# PROC091F_FLASH_USB_TO_UART.net
KiCad netlist of a schematic drawn in Altium Designer
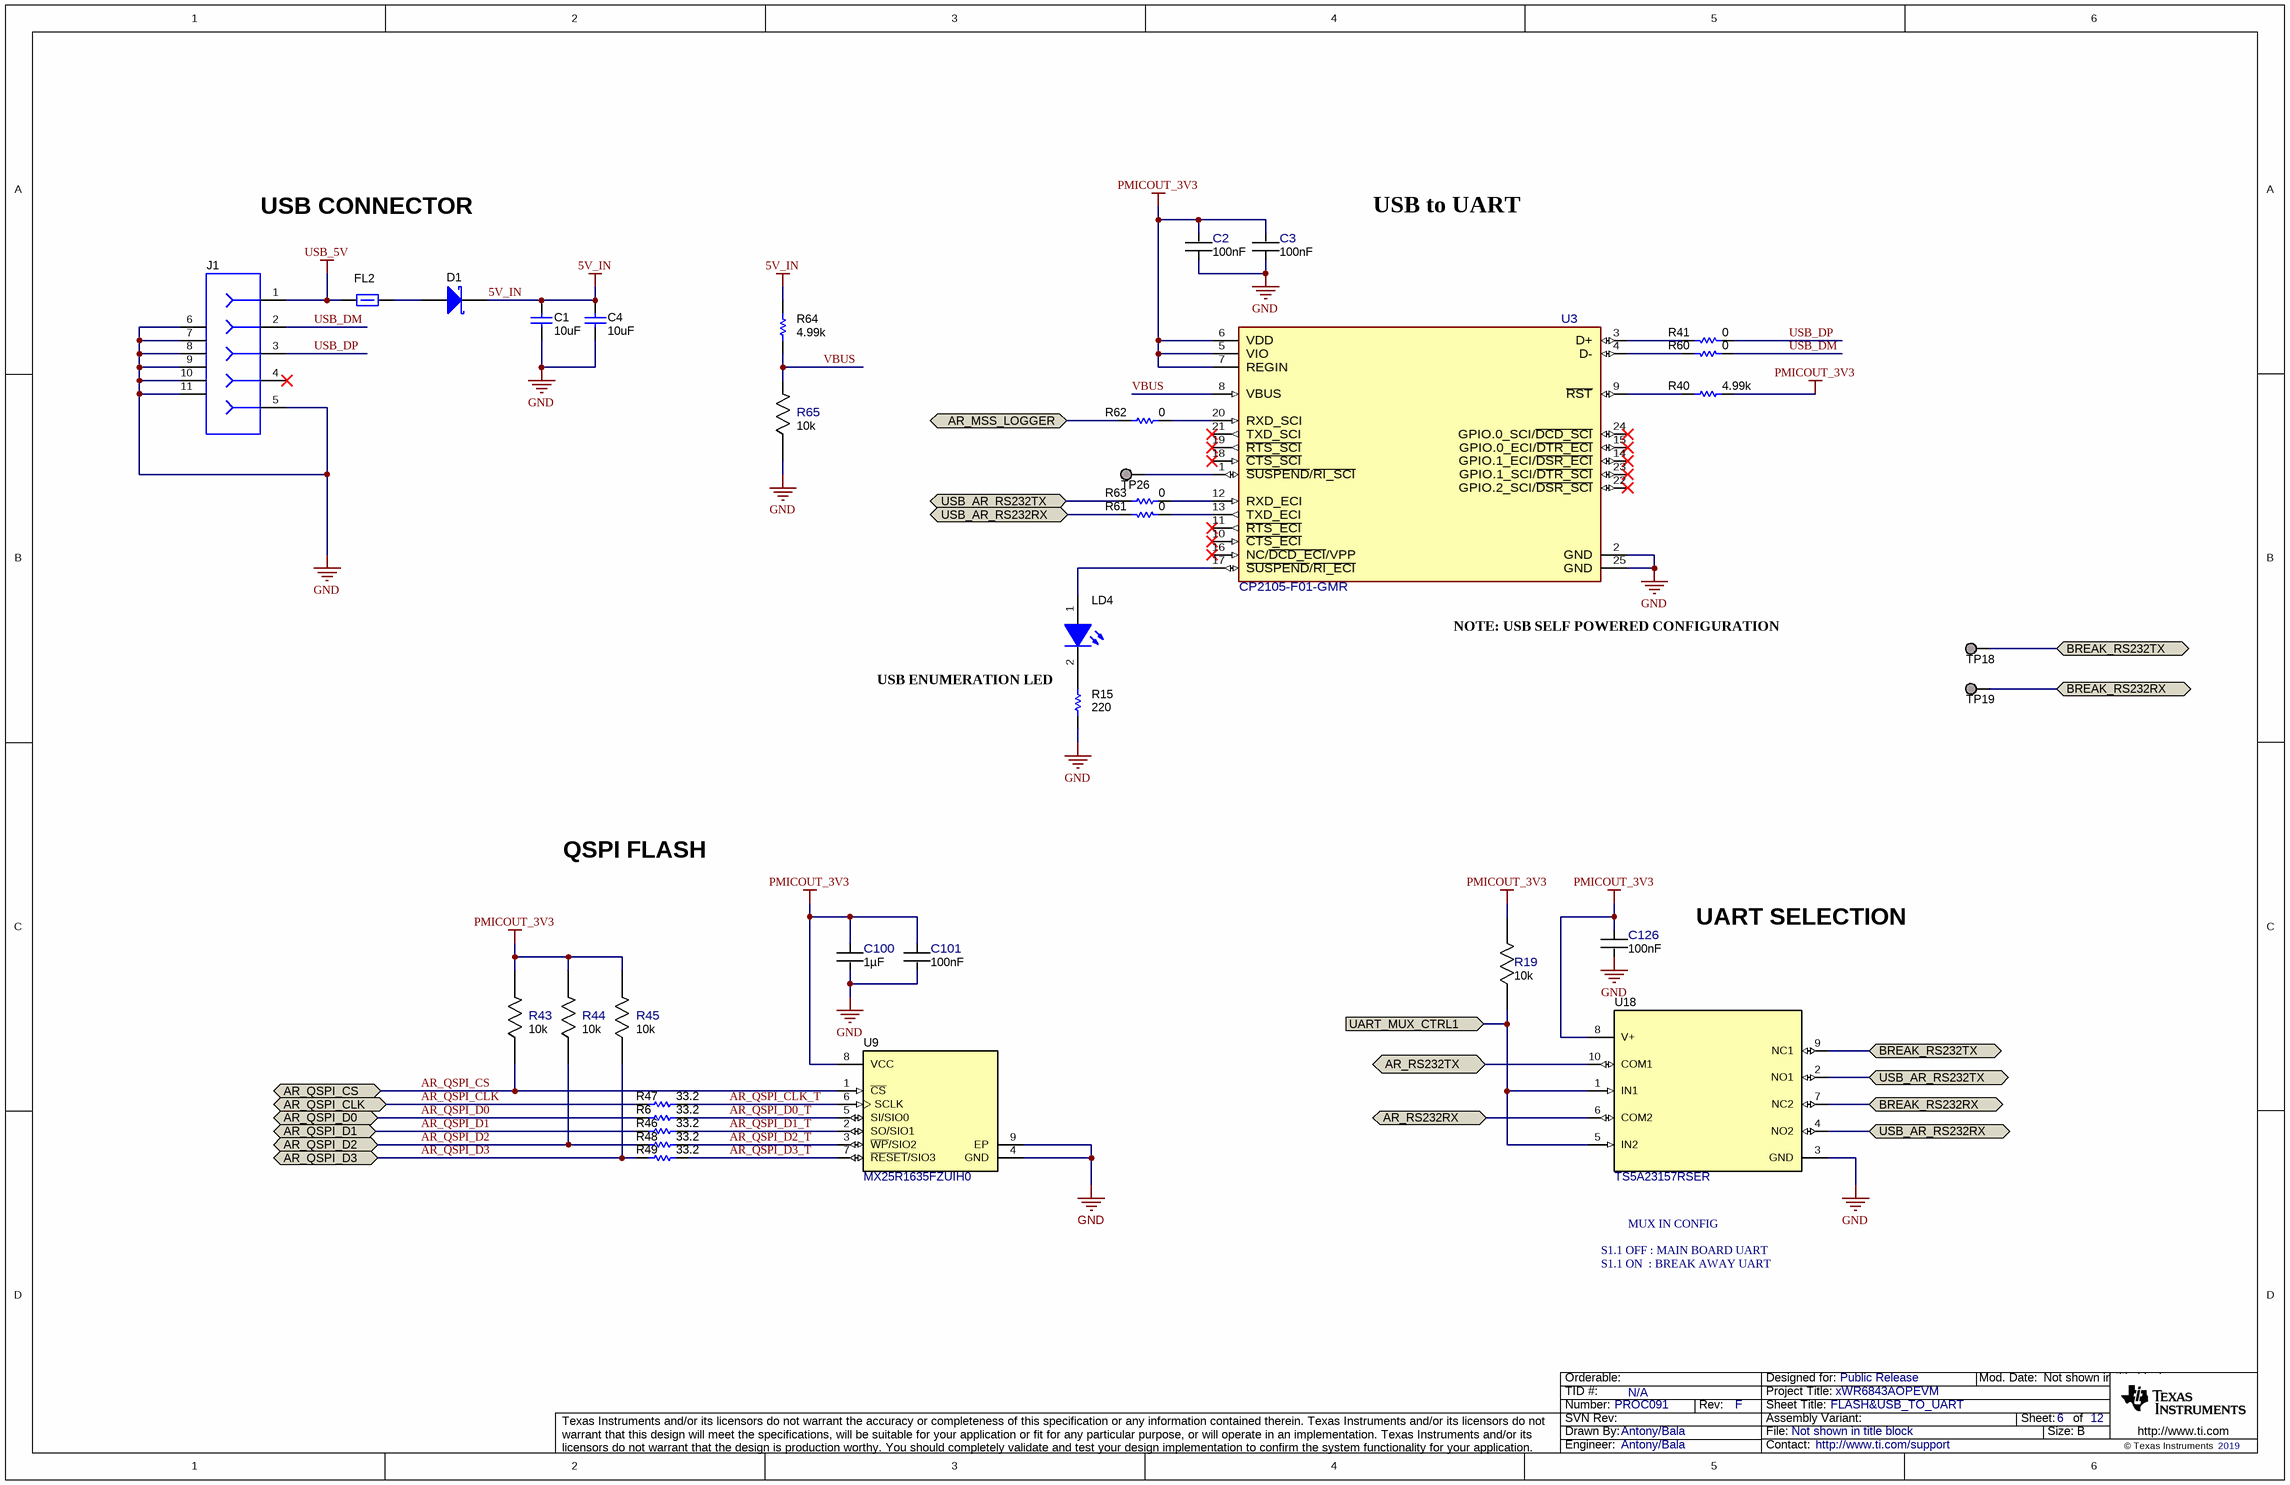
[diagram p0: PROC091F_FLASH_USB_TO_UART.SchDoc]

(export (version "E")
  (design (tool "Eeschema 10.0.6"))
  (components
    (comp (ref "C1")
      (value "10uF")
      (footprint "0402_070")
      (description "CAP, CERM, 10 uF, 10 V, +/- 20%, X5R, 0402")
      (fields
        (field (name "MANUFACTURER") "Samsung Electro-Mechanics")
        (field (name "PARTNUMBER") "CL05A106MP5NUNC")
      )
      (libsource (lib "Altium Vault - TI") (part "Capacitor"))
    )
    (comp (ref "C2")
      (value "GRM033R6YA104KE14D")
      (footprint "FP-GRM033R6YA104KE14D_0201 (0603 Metric)-IPC_C")
      (description "Cap Ceramic 0.1uF 35V X5R 10% Pad SMD 0201 85C T/R")
      (fields (field (name "CAP_F") "100nF") (field (name "MANUFACTURER") "Murata Electronics North America"))
      (libsource (lib "Altium Vault - TI") (part "SYM-B32642B0223J"))
    )
    (comp (ref "C3")
      (value "GRM033R6YA104KE14D")
      (footprint "FP-GRM033R6YA104KE14D_0201 (0603 Metric)-IPC_C")
      (description "Cap Ceramic 0.1uF 35V X5R 10% Pad SMD 0201 85C T/R")
      (fields (field (name "CAP_F") "100nF") (field (name "MANUFACTURER") "Murata Electronics North America"))
      (libsource (lib "Altium Vault - TI") (part "SYM-B32642B0223J"))
    )
    (comp (ref "C4")
      (value "10uF")
      (footprint "0402_070")
      (description "CAP, CERM, 10 uF, 10 V, +/- 20%, X5R, 0402")
      (fields
        (field (name "MANUFACTURER") "Samsung Electro-Mechanics")
        (field (name "PARTNUMBER") "CL05A106MP5NUNC")
      )
      (libsource (lib "Altium Vault - TI") (part "Capacitor"))
    )
    (comp (ref "C100")
      (value "CL03A105MO3NRNH")
      (footprint "FP-CL03A105MO3NRNH_0201-IPC_C")
      (description "1µF ±20% 16V Ceramic Capacitor X5R 0201")
      (fields (field (name "CAP_F") "1µF") (field (name "MANUFACTURER") "Samsung Electro-Mechanics"))
      (libsource (lib "Altium Vault - TI") (part "SYM-B32642B0223J"))
    )
    (comp (ref "C101")
      (value "GRM033R6YA104KE14D")
      (footprint "FP-GRM033R6YA104KE14D_0201 (0603 Metric)-IPC_C")
      (description "Cap Ceramic 0.1uF 35V X5R 10% Pad SMD 0201 85C T/R")
      (fields (field (name "CAP_F") "100nF") (field (name "MANUFACTURER") "Murata Electronics North America"))
      (libsource (lib "Altium Vault - TI") (part "SYM-B32642B0223J"))
    )
    (comp (ref "C126")
      (value "GRM033R6YA104KE14D")
      (footprint "FP-GRM033R6YA104KE14D_0201 (0603 Metric)-IPC_C")
      (description "Cap Ceramic 0.1uF 35V X5R 10% Pad SMD 0201 85C T/R")
      (fields (field (name "CAP_F") "100nF") (field (name "MANUFACTURER") "Murata Electronics North America"))
      (libsource (lib "Altium Vault - TI") (part "SYM-B32642B0223J"))
    )
    (comp (ref "D1")
      (value "NSR20F30NXT5G")
      (footprint "DSN2_0603")
      (description "Diode, Schottky, 30 V, 2 A, 2-XFDFN")
      (fields (field (name "MANUFACTURER") "ON Semiconductor"))
      (libsource (lib "Altium Vault - TI") (part "DIODE_SCHOTTKY"))
    )
    (comp (ref "FL2")
      (value "BLM15PD300SZ1D")
      (footprint "0402L")
      (description "Inductor, Ferrite Bead, Ferrite, 2.2 A, 0.035 ohm, AEC-Q200 Grade 1, SMD")
      (fields (field (name "MANUFACTURER") "MuRata") (field (name "PUBLISHER") "Texas Instruments"))
      (libsource (lib "Altium Vault - TI") (part "Ferrite_Bead"))
    )
    (comp (ref "J1")
      (value "105017-0001")
      (footprint "CONN_105017-0001")
      (description "Connector, Receptacle, Micro-USB Type B, R/A, Bottom Mount SMT")
      (fields (field (name "MANUFACTURER") "Molex") (field (name "PUBLISHER") "Texas Instruments"))
      (libsource (lib "Altium Vault - TI") (part "CONN_105017-0001"))
    )
    (comp (ref "LD4")
      (value "APHHS1005CGCK")
      (footprint "APHHS1005_Green")
      (description "LED, Green, SMD")
      (fields (field (name "MANUFACTURER") "Kingbright"))
      (libsource (lib "Altium Vault - TI") (part "LED"))
    )
    (comp (ref "R6")
      (value "33.2")
      (footprint "0201L")
      (description "RES, 33.2, 1%, 0.05 W, 0201")
      (fields (field (name "MANUFACTURER") "Vishay-Dale") (field (name "PARTNUMBER") "CRCW020133R2FNED"))
      (libsource (lib "Altium Vault - TI") (part "Resistor"))
    )
    (comp (ref "R15")
      (value "220")
      (footprint "0201L")
      (description "RES, 220, 5%, 0.05 W, 0201")
      (fields
        (field (name "MANUFACTURER") "Yageo America")
        (field (name "PARTNUMBER") "RC0201JR-07220RL")
        (field (name "PUBLISHER") "Texas Instruments")
      )
      (libsource (lib "Altium Vault - TI") (part "Resistor"))
    )
    (comp (ref "R19")
      (value "RR0306P-103-D")
      (footprint "FP-RR0306P-103-D_0201-IPC_C")
      (description "10 kOhms ±0.5% 0.05W, 1/20W Chip Resistor 0201 (0603 Metric)  Thin Film")
      (fields (field (name "MANUFACTURER") "Susumu") (field (name "RES_OHM") "10k"))
      (libsource (lib "Altium Vault - TI") (part "SYM-PMR18EZPJ000"))
    )
    (comp (ref "R40")
      (value "4.99k")
      (footprint "0201L")
      (description "RES, 4.99 k, 1%, 0.05 W, 0201")
      (fields
        (field (name "MANUFACTURER") "Yageo America")
        (field (name "PARTNUMBER") "RC0201FR-074K99L")
        (field (name "PUBLISHER") "Texas Instruments")
      )
      (libsource (lib "Altium Vault - TI") (part "Resistor"))
    )
    (comp (ref "R41")
      (value "RC0201JR-070RL")
      (footprint "FP-RC0201JR-070RL_0201 (0603 Metric)-MFG")
      (description "RES SMD 0 OHM JUMPER 1/20W 0201")
      (fields (field (name "MANUFACTURER") "Yageo") (field (name "RES_OHM") "0"))
      (libsource (lib "Altium Vault - TI") (part "SYM-WSR3R1500F"))
    )
    (comp (ref "R43")
      (value "RR0306P-103-D")
      (footprint "FP-RR0306P-103-D_0201-IPC_C")
      (description "10 kOhms ±0.5% 0.05W, 1/20W Chip Resistor 0201 (0603 Metric)  Thin Film")
      (fields (field (name "MANUFACTURER") "Susumu") (field (name "RES_OHM") "10k"))
      (libsource (lib "Altium Vault - TI") (part "SYM-PMR18EZPJ000"))
    )
    (comp (ref "R44")
      (value "RR0306P-103-D")
      (footprint "FP-RR0306P-103-D_0201-IPC_C")
      (description "10 kOhms ±0.5% 0.05W, 1/20W Chip Resistor 0201 (0603 Metric)  Thin Film")
      (fields (field (name "MANUFACTURER") "Susumu") (field (name "RES_OHM") "10k"))
      (libsource (lib "Altium Vault - TI") (part "SYM-PMR18EZPJ000"))
    )
    (comp (ref "R45")
      (value "RR0306P-103-D")
      (footprint "FP-RR0306P-103-D_0201-IPC_C")
      (description "10 kOhms ±0.5% 0.05W, 1/20W Chip Resistor 0201 (0603 Metric)  Thin Film")
      (fields (field (name "MANUFACTURER") "Susumu") (field (name "RES_OHM") "10k"))
      (libsource (lib "Altium Vault - TI") (part "SYM-PMR18EZPJ000"))
    )
    (comp (ref "R46")
      (value "33.2")
      (footprint "0201L")
      (description "RES, 33.2, 1%, 0.05 W, 0201")
      (fields (field (name "MANUFACTURER") "Vishay-Dale") (field (name "PARTNUMBER") "CRCW020133R2FNED"))
      (libsource (lib "Altium Vault - TI") (part "Resistor"))
    )
    (comp (ref "R47")
      (value "33.2")
      (footprint "0201L")
      (description "RES, 33.2, 1%, 0.05 W, 0201")
      (fields (field (name "MANUFACTURER") "Vishay-Dale") (field (name "PARTNUMBER") "CRCW020133R2FNED"))
      (libsource (lib "Altium Vault - TI") (part "Resistor"))
    )
    (comp (ref "R48")
      (value "33.2")
      (footprint "0201L")
      (description "RES, 33.2, 1%, 0.05 W, 0201")
      (fields (field (name "MANUFACTURER") "Vishay-Dale") (field (name "PARTNUMBER") "CRCW020133R2FNED"))
      (libsource (lib "Altium Vault - TI") (part "Resistor"))
    )
    (comp (ref "R49")
      (value "33.2")
      (footprint "0201L")
      (description "RES, 33.2, 1%, 0.05 W, 0201")
      (fields (field (name "MANUFACTURER") "Vishay-Dale") (field (name "PARTNUMBER") "CRCW020133R2FNED"))
      (libsource (lib "Altium Vault - TI") (part "Resistor"))
    )
    (comp (ref "R60")
      (value "RC0201JR-070RL")
      (footprint "FP-RC0201JR-070RL_0201 (0603 Metric)-MFG")
      (description "RES SMD 0 OHM JUMPER 1/20W 0201")
      (fields (field (name "MANUFACTURER") "Yageo") (field (name "RES_OHM") "0"))
      (libsource (lib "Altium Vault - TI") (part "SYM-WSR3R1500F"))
    )
    (comp (ref "R61")
      (value "RC0201JR-070RL")
      (footprint "FP-RC0201JR-070RL_0201 (0603 Metric)-MFG")
      (description "RES SMD 0 OHM JUMPER 1/20W 0201")
      (fields (field (name "MANUFACTURER") "Yageo") (field (name "RES_OHM") "0"))
      (libsource (lib "Altium Vault - TI") (part "SYM-WSR3R1500F"))
    )
    (comp (ref "R62")
      (value "RC0201JR-070RL")
      (footprint "FP-RC0201JR-070RL_0201 (0603 Metric)-MFG")
      (description "RES SMD 0 OHM JUMPER 1/20W 0201")
      (fields (field (name "MANUFACTURER") "Yageo") (field (name "RES_OHM") "0"))
      (libsource (lib "Altium Vault - TI") (part "SYM-WSR3R1500F"))
    )
    (comp (ref "R63")
      (value "RC0201JR-070RL")
      (footprint "FP-RC0201JR-070RL_0201 (0603 Metric)-MFG")
      (description "RES SMD 0 OHM JUMPER 1/20W 0201")
      (fields (field (name "MANUFACTURER") "Yageo") (field (name "RES_OHM") "0"))
      (libsource (lib "Altium Vault - TI") (part "SYM-WSR3R1500F"))
    )
    (comp (ref "R64")
      (value "4.99k")
      (footprint "0201L")
      (description "RES, 4.99 k, 1%, 0.05 W, 0201")
      (fields
        (field (name "MANUFACTURER") "Yageo America")
        (field (name "PARTNUMBER") "RC0201FR-074K99L")
        (field (name "PUBLISHER") "Texas Instruments")
      )
      (libsource (lib "Altium Vault - TI") (part "Resistor"))
    )
    (comp (ref "R65")
      (value "RR0306P-103-D")
      (footprint "FP-RR0306P-103-D_0201-IPC_C")
      (description "10 kOhms ±0.5% 0.05W, 1/20W Chip Resistor 0201 (0603 Metric)  Thin Film")
      (fields (field (name "MANUFACTURER") "Susumu") (field (name "RES_OHM") "10k"))
      (libsource (lib "Altium Vault - TI") (part "SYM-PMR18EZPJ000"))
    )
    (comp (ref "TP18")
      (value "TESTPOINT")
      (footprint "TP_25MIL-SMT")
      (description "TEST POINT.  No entry in BOM.")
      (libsource (lib "Altium Vault - TI") (part "TESTPOINT"))
    )
    (comp (ref "TP19")
      (value "TESTPOINT")
      (footprint "TP_25MIL-SMT")
      (description "TEST POINT.  No entry in BOM.")
      (libsource (lib "Altium Vault - TI") (part "TESTPOINT"))
    )
    (comp (ref "TP26")
      (value "TESTPOINT")
      (footprint "TP_25MIL-SMT")
      (description "TEST POINT.  No entry in BOM.")
      (libsource (lib "Altium Vault - TI") (part "TESTPOINT"))
    )
    (comp (ref "U3")
      (value "CP2105-F01-GMR")
      (footprint "FP-CP2105-F01-GMR_QFN24-EP-IPC_A")
      (description "I/O Controller Interface IC USB to Dual UART bridge")
      (fields (field (name "MANUFACTURER") "Silicon Labs"))
      (libsource (lib "Altium Vault - TI") (part "SYM-CP2105-F01-GMR"))
    )
    (comp (ref "U9")
      (value "MX25R1635FZUIH0")
      (footprint "USON-8L")
      (description "ULTRA LOW POWER, 16M-BIT [x 1/x 2/x 4] CMOS MXSMIO (SERIAL MULTI I/O) FLASH MEMORY, SON-8")
      (fields (field (name "MANUFACTURER") "Macronix International Co., LTD"))
      (libsource (lib "Altium Vault - TI") (part "MX25R1635FZNIH"))
    )
    (comp (ref "U18")
      (value "TS5A23157RSER")
      (footprint "RSE0010A")
      (description "Dual 10-ohm SPDT Analog Switch, RSE0010A (UQFN-10)")
      (fields
        (field (name "MANUFACTURER") "Texas Instruments")
        (field (name "PUBLISHER") "Texas Instruments")
      )
      (libsource (lib "Altium Vault - TI") (part "TS5A23159"))
    )
  )
  (nets
    (net (code "1") (name "/AR_MSS_LOGGER") (class "Default")
      (node (ref "R62") (pin "2") (pinfunction "2_2") (pintype "passive"))
    )
    (net (code "2") (name "/AR_QSPI_CLK") (class "Default")
      (node (ref "R47") (pin "1") (pinfunction "1_1") (pintype "passive"))
    )
    (net (code "3") (name "/AR_QSPI_CLK_T") (class "Default")
      (node (ref "R47") (pin "2") (pinfunction "2_2") (pintype "passive"))
      (node (ref "U9") (pin "6") (pinfunction "SCLK_6") (pintype "input"))
    )
    (net (code "4") (name "/AR_QSPI_CS") (class "Default")
      (node (ref "R43") (pin "1") (pinfunction "1_1") (pintype "passive"))
      (node (ref "U9") (pin "1") (pinfunction "CS_1") (pintype "input"))
    )
    (net (code "5") (name "/AR_QSPI_D0") (class "Default")
      (node (ref "R6") (pin "1") (pinfunction "1_1") (pintype "passive"))
    )
    (net (code "6") (name "/AR_QSPI_D0_T") (class "Default")
      (node (ref "R6") (pin "2") (pinfunction "2_2") (pintype "passive"))
      (node (ref "U9") (pin "5") (pinfunction "SI/SIO0_5") (pintype "bidirectional"))
    )
    (net (code "7") (name "/AR_QSPI_D1") (class "Default")
      (node (ref "R46") (pin "1") (pinfunction "1_1") (pintype "passive"))
    )
    (net (code "8") (name "/AR_QSPI_D1_T") (class "Default")
      (node (ref "R46") (pin "2") (pinfunction "2_2") (pintype "passive"))
      (node (ref "U9") (pin "2") (pinfunction "SO/SIO1_2") (pintype "bidirectional"))
    )
    (net (code "9") (name "/AR_QSPI_D2") (class "Default")
      (node (ref "R44") (pin "1") (pinfunction "1_1") (pintype "passive"))
      (node (ref "R48") (pin "1") (pinfunction "1_1") (pintype "passive"))
    )
    (net (code "10") (name "/AR_QSPI_D2_T") (class "Default")
      (node (ref "R48") (pin "2") (pinfunction "2_2") (pintype "passive"))
      (node (ref "U9") (pin "3") (pinfunction "~{WP}/SIO2_3") (pintype "bidirectional"))
    )
    (net (code "11") (name "/AR_QSPI_D3") (class "Default")
      (node (ref "R45") (pin "1") (pinfunction "1_1") (pintype "passive"))
      (node (ref "R49") (pin "1") (pinfunction "1_1") (pintype "passive"))
    )
    (net (code "12") (name "/AR_QSPI_D3_T") (class "Default")
      (node (ref "R49") (pin "2") (pinfunction "2_2") (pintype "passive"))
      (node (ref "U9") (pin "7") (pinfunction "~{RESET}/SIO3_7") (pintype "bidirectional"))
    )
    (net (code "13") (name "/AR_RS232RX") (class "Default")
      (node (ref "U18") (pin "6") (pinfunction "COM2_6") (pintype "bidirectional"))
    )
    (net (code "14") (name "/AR_RS232TX") (class "Default")
      (node (ref "U18") (pin "10") (pinfunction "COM1_10") (pintype "bidirectional"))
    )
    (net (code "15") (name "/BREAK_RS232RX") (class "Default")
      (node (ref "TP19") (pin "1") (pintype "passive"))
      (node (ref "U18") (pin "7") (pinfunction "NC2_7") (pintype "bidirectional"))
    )
    (net (code "16") (name "/BREAK_RS232TX") (class "Default")
      (node (ref "TP18") (pin "1") (pintype "passive"))
      (node (ref "U18") (pin "9") (pinfunction "NC1_9") (pintype "bidirectional"))
    )
    (net (code "17") (name "/UART_MUX_CTRL1") (class "Default")
      (node (ref "R19") (pin "1") (pinfunction "1_1") (pintype "passive"))
      (node (ref "U18") (pin "1") (pinfunction "IN1_1") (pintype "input"))
      (node (ref "U18") (pin "5") (pinfunction "IN2_5") (pintype "input"))
    )
    (net (code "18") (name "/USB_AR_RS232RX") (class "Default")
      (node (ref "R61") (pin "1") (pinfunction "1_1") (pintype "passive"))
      (node (ref "U18") (pin "4") (pinfunction "NO2_4") (pintype "bidirectional"))
    )
    (net (code "19") (name "/USB_AR_RS232TX") (class "Default")
      (node (ref "R63") (pin "2") (pinfunction "2_2") (pintype "passive"))
      (node (ref "U18") (pin "2") (pinfunction "NO1_2") (pintype "bidirectional"))
    )
    (net (code "20") (name "/USB_DM") (class "Default")
      (node (ref "J1") (pin "2") (pintype "passive"))
      (node (ref "R60") (pin "2") (pinfunction "2_2") (pintype "passive"))
    )
    (net (code "21") (name "/USB_DP") (class "Default")
      (node (ref "J1") (pin "3") (pintype "passive"))
      (node (ref "R41") (pin "2") (pinfunction "2_2") (pintype "passive"))
    )
    (net (code "22") (name "/VBUS") (class "Default")
      (node (ref "R64") (pin "2") (pinfunction "2_2") (pintype "passive"))
      (node (ref "R65") (pin "2") (pinfunction "2_2") (pintype "passive"))
      (node (ref "U3") (pin "8") (pinfunction "VBUS_8") (pintype "input"))
    )
    (net (code "23") (name "5V_IN") (class "Default")
      (node (ref "C1") (pin "2") (pinfunction "2_2") (pintype "passive"))
      (node (ref "C4") (pin "1") (pinfunction "1_1") (pintype "passive"))
      (node (ref "D1") (pin "1") (pinfunction "K_1") (pintype "passive"))
      (node (ref "R64") (pin "1") (pinfunction "1_1") (pintype "passive"))
    )
    (net (code "24") (name "GND") (class "Default")
      (node (ref "C1") (pin "1") (pinfunction "1_1") (pintype "passive"))
      (node (ref "C100") (pin "2") (pinfunction "2_2") (pintype "passive"))
      (node (ref "C101") (pin "2") (pinfunction "2_2") (pintype "passive"))
      (node (ref "C126") (pin "2") (pinfunction "2_2") (pintype "passive"))
      (node (ref "C2") (pin "1") (pinfunction "1_1") (pintype "passive"))
      (node (ref "C3") (pin "1") (pinfunction "1_1") (pintype "passive"))
      (node (ref "C4") (pin "2") (pinfunction "2_2") (pintype "passive"))
      (node (ref "J1") (pin "10") (pintype "passive"))
      (node (ref "J1") (pin "11") (pintype "passive"))
      (node (ref "J1") (pin "5") (pintype "passive"))
      (node (ref "J1") (pin "6") (pintype "passive"))
      (node (ref "J1") (pin "7") (pintype "passive"))
      (node (ref "J1") (pin "8") (pintype "passive"))
      (node (ref "J1") (pin "9") (pintype "passive"))
      (node (ref "R15") (pin "1") (pinfunction "1_1") (pintype "passive"))
      (node (ref "R65") (pin "1") (pinfunction "1_1") (pintype "passive"))
      (node (ref "U18") (pin "3") (pinfunction "GND_3") (pintype "power_in"))
      (node (ref "U3") (pin "2") (pinfunction "GND_2") (pintype "power_in"))
      (node (ref "U3") (pin "25") (pinfunction "GND_25") (pintype "power_in"))
      (node (ref "U9") (pin "4") (pinfunction "GND_4") (pintype "power_in"))
      (node (ref "U9") (pin "9") (pinfunction "EP_9") (pintype "passive"))
    )
    (net (code "25") (name "Net-(D1-A)") (class "Default")
      (node (ref "D1") (pin "2") (pinfunction "A_2") (pintype "passive"))
      (node (ref "FL2") (pin "2") (pinfunction "2_2") (pintype "passive"))
    )
    (net (code "26") (name "Net-(LD4-A)") (class "Default")
      (node (ref "LD4") (pin "1") (pinfunction "A_1") (pintype "passive"))
      (node (ref "U3") (pin "17") (pinfunction "~{SUSPEND}/~{RI_ECI}_17") (pintype "bidirectional"))
    )
    (net (code "27") (name "Net-(LD4-K)") (class "Default")
      (node (ref "LD4") (pin "2") (pinfunction "K_2") (pintype "passive"))
      (node (ref "R15") (pin "2") (pinfunction "2_2") (pintype "passive"))
    )
    (net (code "28") (name "Net-(U3-D+)") (class "Default")
      (node (ref "R41") (pin "1") (pinfunction "1_1") (pintype "passive"))
      (node (ref "U3") (pin "3") (pinfunction "D+_3") (pintype "bidirectional"))
    )
    (net (code "29") (name "Net-(U3-D-)") (class "Default")
      (node (ref "R60") (pin "1") (pinfunction "1_1") (pintype "passive"))
      (node (ref "U3") (pin "4") (pinfunction "D-_4") (pintype "bidirectional"))
    )
    (net (code "30") (name "Net-(U3-RXD_ECI)") (class "Default")
      (node (ref "R63") (pin "1") (pinfunction "1_1") (pintype "passive"))
      (node (ref "U3") (pin "12") (pinfunction "RXD_ECI_12") (pintype "input"))
    )
    (net (code "31") (name "Net-(U3-RXD_SCI)") (class "Default")
      (node (ref "R62") (pin "1") (pinfunction "1_1") (pintype "passive"))
      (node (ref "U3") (pin "20") (pinfunction "RXD_SCI_20") (pintype "input"))
    )
    (net (code "32") (name "Net-(U3-TXD_ECI)") (class "Default")
      (node (ref "R61") (pin "2") (pinfunction "2_2") (pintype "passive"))
      (node (ref "U3") (pin "13") (pinfunction "TXD_ECI_13") (pintype "output"))
    )
    (net (code "33") (name "Net-(U3-~{RST})") (class "Default")
      (node (ref "R40") (pin "2") (pinfunction "2_2") (pintype "passive"))
      (node (ref "U3") (pin "9") (pinfunction "~{RST}_9") (pintype "bidirectional"))
    )
    (net (code "34") (name "Net-(U3-~{SUSPEND}{slash}~{RI_SCI})") (class "Default")
      (node (ref "TP26") (pin "1") (pintype "passive"))
      (node (ref "U3") (pin "1") (pinfunction "~{SUSPEND}/~{RI_SCI}_1") (pintype "bidirectional"))
    )
    (net (code "35") (name "PMICOUT_3V3") (class "Default")
      (node (ref "C100") (pin "1") (pinfunction "1_1") (pintype "passive"))
      (node (ref "C101") (pin "1") (pinfunction "1_1") (pintype "passive"))
      (node (ref "C126") (pin "1") (pinfunction "1_1") (pintype "passive"))
      (node (ref "C2") (pin "2") (pinfunction "2_2") (pintype "passive"))
      (node (ref "C3") (pin "2") (pinfunction "2_2") (pintype "passive"))
      (node (ref "R19") (pin "2") (pinfunction "2_2") (pintype "passive"))
      (node (ref "R40") (pin "1") (pinfunction "1_1") (pintype "passive"))
      (node (ref "R43") (pin "2") (pinfunction "2_2") (pintype "passive"))
      (node (ref "R44") (pin "2") (pinfunction "2_2") (pintype "passive"))
      (node (ref "R45") (pin "2") (pinfunction "2_2") (pintype "passive"))
      (node (ref "U18") (pin "8") (pinfunction "V+_8") (pintype "power_in"))
      (node (ref "U3") (pin "5") (pinfunction "VIO_5") (pintype "power_in"))
      (node (ref "U3") (pin "6") (pinfunction "VDD_6") (pintype "power_in"))
      (node (ref "U3") (pin "7") (pinfunction "REGIN_7") (pintype "power_in"))
      (node (ref "U9") (pin "8") (pinfunction "VCC_8") (pintype "power_in"))
    )
    (net (code "36") (name "USB_5V") (class "Default")
      (node (ref "FL2") (pin "1") (pinfunction "1_1") (pintype "passive"))
      (node (ref "J1") (pin "1") (pintype "passive"))
    )
    (net (code "37") (name "unconnected-(J1-Pad4)") (class "Default")
      (node (ref "J1") (pin "4") (pintype "passive+no_connect"))
    )
    (net (code "38") (name "unconnected-(U3-GPIO.0_ECI{slash}~{DTR_ECI}-Pad15)") (class "Default")
      (node (ref "U3") (pin "15") (pinfunction "GPIO.0_ECI/~{DTR_ECI}_15") (pintype "bidirectional+no_connect"))
    )
    (net (code "39") (name "unconnected-(U3-GPIO.0_SCI{slash}~{DCD_SCI}-Pad24)") (class "Default")
      (node (ref "U3") (pin "24") (pinfunction "GPIO.0_SCI/~{DCD_SCI}_24") (pintype "bidirectional+no_connect"))
    )
    (net (code "40") (name "unconnected-(U3-GPIO.1_ECI{slash}~{DSR_ECI}-Pad14)") (class "Default")
      (node (ref "U3") (pin "14") (pinfunction "GPIO.1_ECI/~{DSR_ECI}_14") (pintype "bidirectional+no_connect"))
    )
    (net (code "41") (name "unconnected-(U3-GPIO.1_SCI{slash}~{DTR_SCI}-Pad23)") (class "Default")
      (node (ref "U3") (pin "23") (pinfunction "GPIO.1_SCI/~{DTR_SCI}_23") (pintype "bidirectional+no_connect"))
    )
    (net (code "42") (name "unconnected-(U3-GPIO.2_SCI{slash}~{DSR_SCI}-Pad22)") (class "Default")
      (node (ref "U3") (pin "22") (pinfunction "GPIO.2_SCI/~{DSR_SCI}_22") (pintype "bidirectional+no_connect"))
    )
    (net (code "43") (name "unconnected-(U3-NC{slash}~{DCD_ECI}{slash}VPP-Pad16)") (class "Default")
      (node (ref "U3") (pin "16") (pinfunction "NC/~{DCD_ECI}/VPP_16") (pintype "input+no_connect"))
    )
    (net (code "44") (name "unconnected-(U3-TXD_SCI-Pad21)") (class "Default")
      (node (ref "U3") (pin "21") (pinfunction "TXD_SCI_21") (pintype "output+no_connect"))
    )
    (net (code "45") (name "unconnected-(U3-~{CTS_ECI}-Pad10)") (class "Default")
      (node (ref "U3") (pin "10") (pinfunction "~{CTS_ECI}_10") (pintype "input+no_connect"))
    )
    (net (code "46") (name "unconnected-(U3-~{CTS_SCI}-Pad18)") (class "Default")
      (node (ref "U3") (pin "18") (pinfunction "~{CTS_SCI}_18") (pintype "input+no_connect"))
    )
    (net (code "47") (name "unconnected-(U3-~{RTS_ECI}-Pad11)") (class "Default")
      (node (ref "U3") (pin "11") (pinfunction "~{RTS_ECI}_11") (pintype "output+no_connect"))
    )
    (net (code "48") (name "unconnected-(U3-~{RTS_SCI}-Pad19)") (class "Default")
      (node (ref "U3") (pin "19") (pinfunction "~{RTS_SCI}_19") (pintype "output+no_connect"))
    )
  )
)
